# azo_overdrive.net
KiCad netlist of a schematic drawn in EAGLE
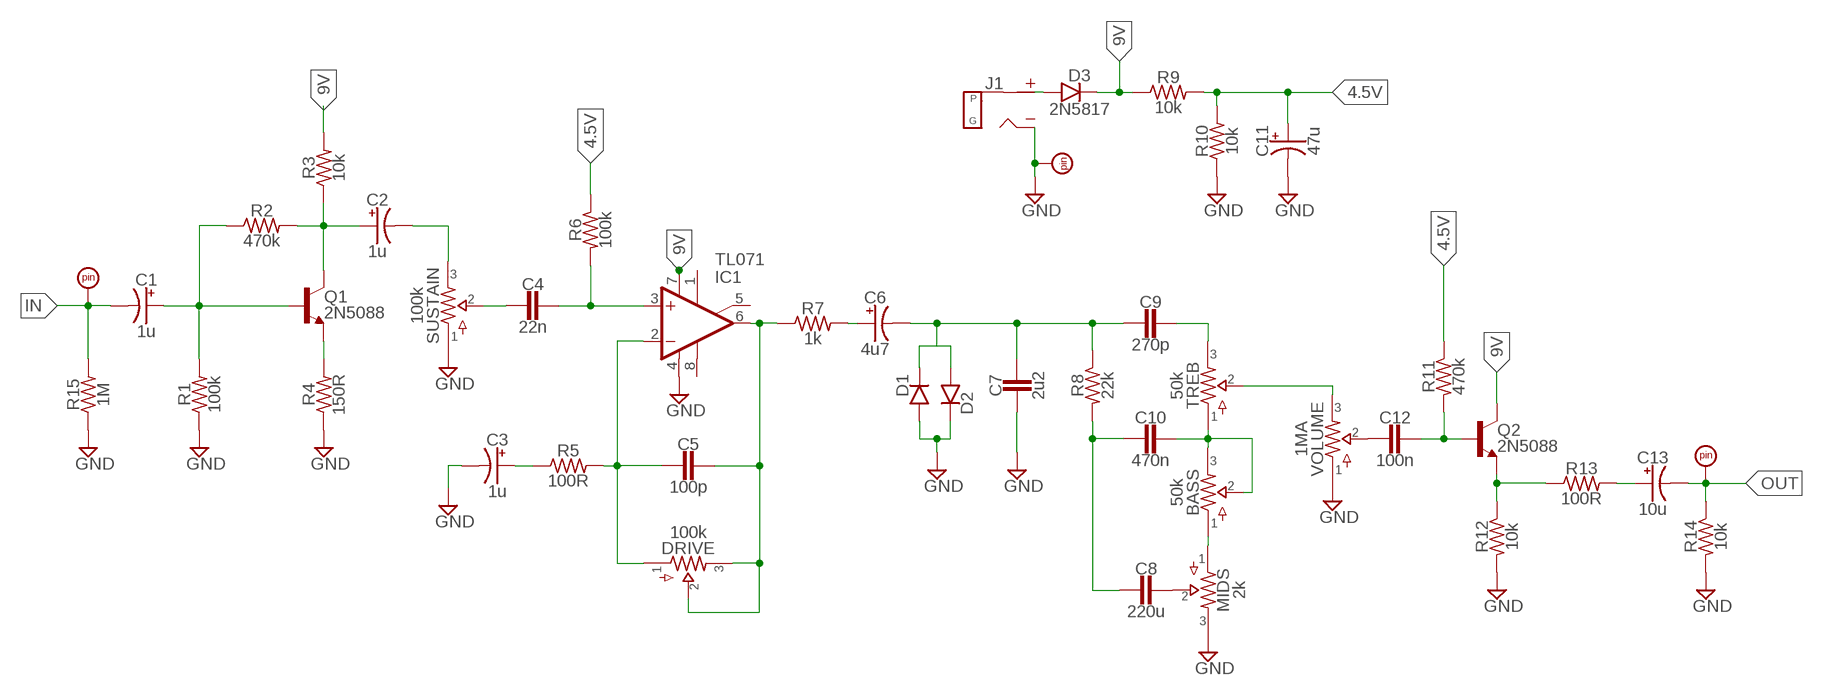
[diagram p0: schematic, sheet 1]

(export (version "E")
  (design (tool "Eeschema 10.0.6"))
  (components
    (comp (ref "BASS")
      (value "50k")
      (footprint "eagle-import:16MM")
      (libsource (lib "eagle-import") (part "POTS16MM"))
    )
    (comp (ref "C1")
      (value "1u")
      (footprint "eagle-import:050_020_1")
      (libsource (lib "eagle-import") (part "0501"))
    )
    (comp (ref "C2")
      (value "1u")
      (footprint "eagle-import:050_020_1")
      (libsource (lib "eagle-import") (part "0501"))
    )
    (comp (ref "C3")
      (value "1u")
      (footprint "eagle-import:050_020_1")
      (libsource (lib "eagle-import") (part "0501"))
    )
    (comp (ref "C4")
      (value "22n")
      (footprint "eagle-import:050X030_025_2")
      (libsource (lib "eagle-import") (part "CER/FILM2"))
    )
    (comp (ref "C5")
      (value "100p")
      (footprint "eagle-import:050X030_025_2")
      (libsource (lib "eagle-import") (part "CER/FILM2"))
    )
    (comp (ref "C6")
      (value "4u7")
      (footprint "eagle-import:050_020_1")
      (libsource (lib "eagle-import") (part "0501"))
    )
    (comp (ref "C7")
      (value "2u2")
      (footprint "eagle-import:050X030_025_2")
      (libsource (lib "eagle-import") (part "CER/FILM2"))
    )
    (comp (ref "C8")
      (value "220u")
      (footprint "eagle-import:050X030_025_2")
      (libsource (lib "eagle-import") (part "CER/FILM2"))
    )
    (comp (ref "C9")
      (value "270p")
      (footprint "eagle-import:050X030_025_2")
      (libsource (lib "eagle-import") (part "CER/FILM2"))
    )
    (comp (ref "C10")
      (value "470n")
      (footprint "eagle-import:050X030_025_2")
      (libsource (lib "eagle-import") (part "CER/FILM2"))
    )
    (comp (ref "C11")
      (value "47u")
      (footprint "eagle-import:050_020_1")
      (libsource (lib "eagle-import") (part "0501"))
    )
    (comp (ref "C12")
      (value "100n")
      (footprint "eagle-import:050X030_025_2")
      (libsource (lib "eagle-import") (part "CER/FILM2"))
    )
    (comp (ref "C13")
      (value "10u")
      (footprint "eagle-import:050_020_1")
      (libsource (lib "eagle-import") (part "0501"))
    )
    (comp (ref "D1")
      (value "DO35.2")
      (footprint "eagle-import:DO35-2")
      (libsource (lib "eagle-import") (part "DO35.2"))
    )
    (comp (ref "D2")
      (value "DO35.2")
      (footprint "eagle-import:DO35-2")
      (libsource (lib "eagle-import") (part "DO35.2"))
    )
    (comp (ref "D3")
      (value "2N5817")
      (footprint "eagle-import:DO41-3")
      (libsource (lib "eagle-import") (part "DO41.3"))
    )
    (comp (ref "DRIVE")
      (value "100k")
      (footprint "eagle-import:16MM")
      (libsource (lib "eagle-import") (part "POTS16MM"))
    )
    (comp (ref "GND")
      (value "PADSQR")
      (footprint "eagle-import:SQUARE")
      (libsource (lib "eagle-import") (part "PADSQR"))
    )
    (comp (ref "IC1")
      (value "TL071")
      (footprint "eagle-import:DIL08")
      (libsource (lib "eagle-import") (part "SINGLETH"))
    )
    (comp (ref "IN")
      (value "PADSQR")
      (footprint "eagle-import:SQUARE")
      (libsource (lib "eagle-import") (part "PADSQR"))
    )
    (comp (ref "J1")
      (value "DC_MONO")
      (footprint "eagle-import:DC")
      (libsource (lib "eagle-import") (part "DC_MONO"))
    )
    (comp (ref "MIDS")
      (value "2k")
      (footprint "eagle-import:16MM")
      (libsource (lib "eagle-import") (part "POTS16MM"))
    )
    (comp (ref "OUT")
      (value "PADSQR")
      (footprint "eagle-import:SQUARE")
      (libsource (lib "eagle-import") (part "PADSQR"))
    )
    (comp (ref "Q1")
      (value "2N5088")
      (footprint "eagle-import:TO92-")
      (libsource (lib "eagle-import") (part "2N5088"))
    )
    (comp (ref "Q2")
      (value "2N5088")
      (footprint "eagle-import:TO92-")
      (libsource (lib "eagle-import") (part "2N5088"))
    )
    (comp (ref "R1")
      (value "100k")
      (footprint "eagle-import:R0207_3")
      (libsource (lib "eagle-import") (part "R_.3B"))
    )
    (comp (ref "R2")
      (value "470k")
      (footprint "eagle-import:R0207_3")
      (libsource (lib "eagle-import") (part "R_.3B"))
    )
    (comp (ref "R3")
      (value "10k")
      (footprint "eagle-import:R0207_3")
      (libsource (lib "eagle-import") (part "R_.3B"))
    )
    (comp (ref "R4")
      (value "150R")
      (footprint "eagle-import:R0207_3")
      (libsource (lib "eagle-import") (part "R_.3B"))
    )
    (comp (ref "R5")
      (value "100R")
      (footprint "eagle-import:R0207_3")
      (libsource (lib "eagle-import") (part "R_.3B"))
    )
    (comp (ref "R6")
      (value "100k")
      (footprint "eagle-import:R0207_3")
      (libsource (lib "eagle-import") (part "R_.3B"))
    )
    (comp (ref "R7")
      (value "1k")
      (footprint "eagle-import:R0207_3")
      (libsource (lib "eagle-import") (part "R_.3B"))
    )
    (comp (ref "R8")
      (value "22k")
      (footprint "eagle-import:R0207_3")
      (libsource (lib "eagle-import") (part "R_.3B"))
    )
    (comp (ref "R9")
      (value "10k")
      (footprint "eagle-import:R0207_3")
      (libsource (lib "eagle-import") (part "R_.3B"))
    )
    (comp (ref "R10")
      (value "10k")
      (footprint "eagle-import:R0207_3")
      (libsource (lib "eagle-import") (part "R_.3B"))
    )
    (comp (ref "R11")
      (value "470k")
      (footprint "eagle-import:R0207_3")
      (libsource (lib "eagle-import") (part "R_.3B"))
    )
    (comp (ref "R12")
      (value "10k")
      (footprint "eagle-import:R0207_3")
      (libsource (lib "eagle-import") (part "R_.3B"))
    )
    (comp (ref "R13")
      (value "100R")
      (footprint "eagle-import:R0207_3")
      (libsource (lib "eagle-import") (part "R_.3B"))
    )
    (comp (ref "R14")
      (value "10k")
      (footprint "eagle-import:R0207_3")
      (libsource (lib "eagle-import") (part "R_.3B"))
    )
    (comp (ref "R15")
      (value "1M")
      (footprint "eagle-import:R0207_3")
      (libsource (lib "eagle-import") (part "R_.3B"))
    )
    (comp (ref "SUSTAIN")
      (value "100k")
      (footprint "eagle-import:2262_TRIM")
      (libsource (lib "eagle-import") (part "POTSTRIM"))
    )
    (comp (ref "TREB")
      (value "50k")
      (footprint "eagle-import:16MM")
      (libsource (lib "eagle-import") (part "POTS16MM"))
    )
    (comp (ref "VOLUME")
      (value "1MA")
      (footprint "eagle-import:16MM")
      (libsource (lib "eagle-import") (part "POTS16MM"))
    )
  )
  (nets
    (net (code "1") (name "4.5V") (class "Default")
      (node (ref "C11") (pin "+") (pinfunction "+_+") (pintype "passive"))
      (node (ref "R10") (pin "2") (pinfunction "2_2") (pintype "passive"))
      (node (ref "R11") (pin "1") (pinfunction "1_1") (pintype "passive"))
      (node (ref "R6") (pin "1") (pinfunction "1_1") (pintype "passive"))
      (node (ref "R9") (pin "2") (pinfunction "2_2") (pintype "passive"))
    )
    (net (code "2") (name "9V") (class "Default")
      (node (ref "D3") (pin "C") (pinfunction "C_C") (pintype "passive"))
      (node (ref "IC1") (pin "7") (pinfunction "V+_7") (pintype "power_in"))
      (node (ref "Q2") (pin "1") (pinfunction "C_1") (pintype "passive"))
      (node (ref "R3") (pin "2") (pinfunction "2_2") (pintype "passive"))
      (node (ref "R9") (pin "1") (pinfunction "1_1") (pintype "passive"))
    )
    (net (code "3") (name "GND") (class "Default")
      (node (ref "C11") (pin "-") (pinfunction "-_-") (pintype "passive"))
      (node (ref "C3") (pin "-") (pinfunction "-_-") (pintype "passive"))
      (node (ref "C7") (pin "2") (pinfunction "2_2") (pintype "passive"))
      (node (ref "D1") (pin "A") (pinfunction "A_A") (pintype "passive"))
      (node (ref "D2") (pin "C") (pinfunction "C_C") (pintype "passive"))
      (node (ref "GND") (pin "1") (pinfunction "P$1_1") (pintype "bidirectional"))
      (node (ref "IC1") (pin "4") (pinfunction "V-_4") (pintype "power_in"))
      (node (ref "J1") (pin "S") (pinfunction "SLEEVE_S") (pintype "passive"))
      (node (ref "MIDS") (pin "3") (pinfunction "3_3") (pintype "passive"))
      (node (ref "R1") (pin "1") (pinfunction "1_1") (pintype "passive"))
      (node (ref "R10") (pin "1") (pinfunction "1_1") (pintype "passive"))
      (node (ref "R12") (pin "2") (pinfunction "2_2") (pintype "passive"))
      (node (ref "R14") (pin "2") (pinfunction "2_2") (pintype "passive"))
      (node (ref "R15") (pin "1") (pinfunction "1_1") (pintype "passive"))
      (node (ref "R4") (pin "1") (pinfunction "1_1") (pintype "passive"))
      (node (ref "SUSTAIN") (pin "1") (pinfunction "1_1") (pintype "passive"))
      (node (ref "VOLUME") (pin "1") (pinfunction "1_1") (pintype "passive"))
    )
    (net (code "4") (name "IN") (class "Default")
      (node (ref "C1") (pin "-") (pinfunction "-_-") (pintype "passive"))
      (node (ref "IN") (pin "1") (pinfunction "P$1_1") (pintype "bidirectional"))
      (node (ref "R15") (pin "2") (pinfunction "2_2") (pintype "passive"))
    )
    (net (code "5") (name "Net-(BASS-Pad1)") (class "Default")
      (node (ref "BASS") (pin "1") (pinfunction "1_1") (pintype "passive"))
      (node (ref "MIDS") (pin "1") (pinfunction "1_1") (pintype "passive"))
    )
    (net (code "6") (name "Net-(BASS-Pad2)") (class "Default")
      (node (ref "BASS") (pin "2") (pinfunction "2_2") (pintype "passive"))
      (node (ref "BASS") (pin "3") (pinfunction "3_3") (pintype "passive"))
      (node (ref "C10") (pin "1") (pinfunction "1_1") (pintype "passive"))
      (node (ref "TREB") (pin "1") (pinfunction "1_1") (pintype "passive"))
    )
    (net (code "7") (name "Net-(C2-Pad-)") (class "Default")
      (node (ref "C2") (pin "-") (pinfunction "-_-") (pintype "passive"))
      (node (ref "SUSTAIN") (pin "3") (pinfunction "3_3") (pintype "passive"))
    )
    (net (code "8") (name "Net-(C3-Pad+)") (class "Default")
      (node (ref "C3") (pin "+") (pinfunction "+_+") (pintype "passive"))
      (node (ref "R5") (pin "1") (pinfunction "1_1") (pintype "passive"))
    )
    (net (code "9") (name "Net-(C4-Pad2)") (class "Default")
      (node (ref "C4") (pin "2") (pinfunction "2_2") (pintype "passive"))
      (node (ref "SUSTAIN") (pin "2") (pinfunction "2_2") (pintype "passive"))
    )
    (net (code "10") (name "Net-(C6-Pad+)") (class "Default")
      (node (ref "C6") (pin "+") (pinfunction "+_+") (pintype "passive"))
      (node (ref "R7") (pin "2") (pinfunction "2_2") (pintype "passive"))
    )
    (net (code "11") (name "Net-(C6-Pad-)") (class "Default")
      (node (ref "C6") (pin "-") (pinfunction "-_-") (pintype "passive"))
      (node (ref "C7") (pin "1") (pinfunction "1_1") (pintype "passive"))
      (node (ref "C9") (pin "2") (pinfunction "2_2") (pintype "passive"))
      (node (ref "D1") (pin "C") (pinfunction "C_C") (pintype "passive"))
      (node (ref "D2") (pin "A") (pinfunction "A_A") (pintype "passive"))
      (node (ref "R8") (pin "1") (pinfunction "1_1") (pintype "passive"))
    )
    (net (code "12") (name "Net-(C8-Pad1)") (class "Default")
      (node (ref "C8") (pin "1") (pinfunction "1_1") (pintype "passive"))
      (node (ref "MIDS") (pin "2") (pinfunction "2_2") (pintype "passive"))
    )
    (net (code "13") (name "Net-(C9-Pad1)") (class "Default")
      (node (ref "C9") (pin "1") (pinfunction "1_1") (pintype "passive"))
      (node (ref "TREB") (pin "3") (pinfunction "3_3") (pintype "passive"))
    )
    (net (code "14") (name "Net-(C10-Pad2)") (class "Default")
      (node (ref "C10") (pin "2") (pinfunction "2_2") (pintype "passive"))
      (node (ref "C8") (pin "2") (pinfunction "2_2") (pintype "passive"))
      (node (ref "R8") (pin "2") (pinfunction "2_2") (pintype "passive"))
    )
    (net (code "15") (name "Net-(C12-Pad2)") (class "Default")
      (node (ref "C12") (pin "2") (pinfunction "2_2") (pintype "passive"))
      (node (ref "VOLUME") (pin "2") (pinfunction "2_2") (pintype "passive"))
    )
    (net (code "16") (name "Net-(C13-Pad+)") (class "Default")
      (node (ref "C13") (pin "+") (pinfunction "+_+") (pintype "passive"))
      (node (ref "R13") (pin "2") (pinfunction "2_2") (pintype "passive"))
    )
    (net (code "17") (name "Net-(IC1-+IN)") (class "Default")
      (node (ref "C4") (pin "1") (pinfunction "1_1") (pintype "passive"))
      (node (ref "IC1") (pin "3") (pinfunction "+IN_3") (pintype "input"))
      (node (ref "R6") (pin "2") (pinfunction "2_2") (pintype "passive"))
    )
    (net (code "18") (name "Net-(IC1--IN)") (class "Default")
      (node (ref "C5") (pin "2") (pinfunction "2_2") (pintype "passive"))
      (node (ref "DRIVE") (pin "1") (pinfunction "1_1") (pintype "passive"))
      (node (ref "IC1") (pin "2") (pinfunction "-IN_2") (pintype "input"))
      (node (ref "R5") (pin "2") (pinfunction "2_2") (pintype "passive"))
    )
    (net (code "19") (name "Net-(IC1-OUT)") (class "Default")
      (node (ref "C5") (pin "1") (pinfunction "1_1") (pintype "passive"))
      (node (ref "DRIVE") (pin "2") (pinfunction "2_2") (pintype "passive"))
      (node (ref "DRIVE") (pin "3") (pinfunction "3_3") (pintype "passive"))
      (node (ref "IC1") (pin "6") (pinfunction "OUT_6") (pintype "output"))
      (node (ref "R7") (pin "1") (pinfunction "1_1") (pintype "passive"))
    )
    (net (code "20") (name "Net-(J1-TIP)") (class "Default")
      (node (ref "D3") (pin "A") (pinfunction "A_A") (pintype "passive"))
      (node (ref "J1") (pin "T") (pinfunction "TIP_T") (pintype "passive"))
    )
    (net (code "21") (name "Net-(Q1-B)") (class "Default")
      (node (ref "C1") (pin "+") (pinfunction "+_+") (pintype "passive"))
      (node (ref "Q1") (pin "2") (pinfunction "B_2") (pintype "passive"))
      (node (ref "R1") (pin "2") (pinfunction "2_2") (pintype "passive"))
      (node (ref "R2") (pin "1") (pinfunction "1_1") (pintype "passive"))
    )
    (net (code "22") (name "Net-(Q1-C)") (class "Default")
      (node (ref "C2") (pin "+") (pinfunction "+_+") (pintype "passive"))
      (node (ref "Q1") (pin "1") (pinfunction "C_1") (pintype "passive"))
      (node (ref "R2") (pin "2") (pinfunction "2_2") (pintype "passive"))
      (node (ref "R3") (pin "1") (pinfunction "1_1") (pintype "passive"))
    )
    (net (code "23") (name "Net-(Q1-E)") (class "Default")
      (node (ref "Q1") (pin "3") (pinfunction "E_3") (pintype "passive"))
      (node (ref "R4") (pin "2") (pinfunction "2_2") (pintype "passive"))
    )
    (net (code "24") (name "Net-(Q2-B)") (class "Default")
      (node (ref "C12") (pin "1") (pinfunction "1_1") (pintype "passive"))
      (node (ref "Q2") (pin "2") (pinfunction "B_2") (pintype "passive"))
      (node (ref "R11") (pin "2") (pinfunction "2_2") (pintype "passive"))
    )
    (net (code "25") (name "Net-(Q2-E)") (class "Default")
      (node (ref "Q2") (pin "3") (pinfunction "E_3") (pintype "passive"))
      (node (ref "R12") (pin "1") (pinfunction "1_1") (pintype "passive"))
      (node (ref "R13") (pin "1") (pinfunction "1_1") (pintype "passive"))
    )
    (net (code "26") (name "Net-(TREB-Pad2)") (class "Default")
      (node (ref "TREB") (pin "2") (pinfunction "2_2") (pintype "passive"))
      (node (ref "VOLUME") (pin "3") (pinfunction "3_3") (pintype "passive"))
    )
    (net (code "27") (name "OUT") (class "Default")
      (node (ref "C13") (pin "-") (pinfunction "-_-") (pintype "passive"))
      (node (ref "OUT") (pin "1") (pinfunction "P$1_1") (pintype "bidirectional"))
      (node (ref "R14") (pin "1") (pinfunction "1_1") (pintype "passive"))
    )
    (net (code "28") (name "unconnected-(IC1-ON1-Pad1)") (class "Default")
      (node (ref "IC1") (pin "1") (pinfunction "ON1_1") (pintype "passive"))
    )
    (net (code "29") (name "unconnected-(IC1-ON2-Pad5)") (class "Default")
      (node (ref "IC1") (pin "5") (pinfunction "ON2_5") (pintype "passive"))
    )
    (net (code "30") (name "unconnected-(IC1-OPT-Pad8)") (class "Default")
      (node (ref "IC1") (pin "8") (pinfunction "OPT_8") (pintype "passive"))
    )
  )
)
